# Main_ASCII.net
KiCad netlist of a schematic drawn in Altium Designer
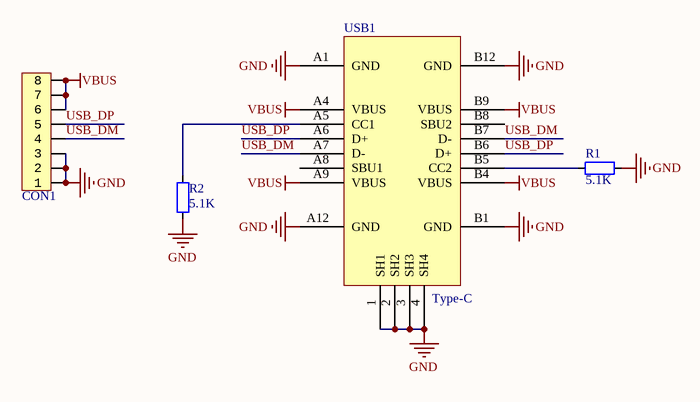
[diagram p0: Main_ASCII.SchDoc]

(export (version "E")
  (design (tool "Eeschema 10.0.6"))
  (components
    (comp (ref "CON1")
      (value "FFC_0.5_8")
      (footprint "FFC_0.5_8")
      (description "FFC")
      (libsource (lib "KitSprout") (part "FFC_0.5_8"))
    )
    (comp (ref "R1")
      (value "5.1K")
      (footprint "RES_0402")
      (description "Resistor")
      (libsource (lib "MyPcbLib") (part "电阻-0402"))
    )
    (comp (ref "R2")
      (value "5.1K")
      (footprint "RES_0402")
      (description "Resistor")
      (libsource (lib "") (part "电阻-0402_1"))
    )
    (comp (ref "USB1")
      (value "Type-C")
      (footprint "Type-C-TOP")
      (libsource (lib "MyPcbLib") (part "USB-Type-C-TOP"))
    )
  )
  (nets
    (net (code "1") (name "/USB_DM") (class "Default")
      (node (ref "CON1") (pin "4") (pinfunction "4_4") (pintype "passive"))
      (node (ref "USB1") (pin "A7") (pinfunction "D-_A7") (pintype "passive"))
      (node (ref "USB1") (pin "B7") (pinfunction "D-_B7") (pintype "passive"))
    )
    (net (code "2") (name "/USB_DP") (class "Default")
      (node (ref "CON1") (pin "5") (pinfunction "5_5") (pintype "passive"))
      (node (ref "USB1") (pin "A6") (pinfunction "D+_A6") (pintype "passive"))
      (node (ref "USB1") (pin "B6") (pinfunction "D+_B6") (pintype "passive"))
    )
    (net (code "3") (name "GND") (class "Default")
      (node (ref "CON1") (pin "1") (pinfunction "1_1") (pintype "passive"))
      (node (ref "CON1") (pin "2") (pinfunction "2_2") (pintype "passive"))
      (node (ref "CON1") (pin "3") (pinfunction "3_3") (pintype "passive"))
      (node (ref "R1") (pin "1") (pinfunction "1_1") (pintype "passive"))
      (node (ref "R2") (pin "2") (pinfunction "2_2") (pintype "passive"))
      (node (ref "USB1") (pin "1") (pinfunction "SH1_1") (pintype "passive"))
      (node (ref "USB1") (pin "2") (pinfunction "SH2_2") (pintype "passive"))
      (node (ref "USB1") (pin "3") (pinfunction "SH3_3") (pintype "passive"))
      (node (ref "USB1") (pin "4") (pinfunction "SH4_4") (pintype "passive"))
      (node (ref "USB1") (pin "A1") (pinfunction "GND_A1") (pintype "passive"))
      (node (ref "USB1") (pin "A12") (pinfunction "GND_A12") (pintype "passive"))
      (node (ref "USB1") (pin "B1") (pinfunction "GND_B1") (pintype "passive"))
      (node (ref "USB1") (pin "B12") (pinfunction "GND_B12") (pintype "passive"))
    )
    (net (code "4") (name "Net-(USB1-CC1)") (class "Default")
      (node (ref "R2") (pin "1") (pinfunction "1_1") (pintype "passive"))
      (node (ref "USB1") (pin "A5") (pinfunction "CC1_A5") (pintype "passive"))
    )
    (net (code "5") (name "Net-(USB1-CC2)") (class "Default")
      (node (ref "R1") (pin "2") (pinfunction "2_2") (pintype "passive"))
      (node (ref "USB1") (pin "B5") (pinfunction "CC2_B5") (pintype "passive"))
    )
    (net (code "6") (name "VBUS") (class "Default")
      (node (ref "CON1") (pin "6") (pinfunction "6_6") (pintype "passive"))
      (node (ref "CON1") (pin "7") (pinfunction "7_7") (pintype "passive"))
      (node (ref "CON1") (pin "8") (pinfunction "8_8") (pintype "passive"))
      (node (ref "USB1") (pin "A4") (pinfunction "VBUS_A4") (pintype "passive"))
      (node (ref "USB1") (pin "A9") (pinfunction "VBUS_A9") (pintype "passive"))
      (node (ref "USB1") (pin "B4") (pinfunction "VBUS_B4") (pintype "passive"))
      (node (ref "USB1") (pin "B9") (pinfunction "VBUS_B9") (pintype "passive"))
    )
    (net (code "7") (name "unconnected-(USB1-SBU1-PadA8)") (class "Default")
      (node (ref "USB1") (pin "A8") (pinfunction "SBU1_A8") (pintype "passive"))
    )
    (net (code "8") (name "unconnected-(USB1-SBU2-PadB8)") (class "Default")
      (node (ref "USB1") (pin "B8") (pinfunction "SBU2_B8") (pintype "passive"))
    )
  )
)
